# JTAG_Connector.net
KiCad netlist of a schematic drawn in Altium Designer
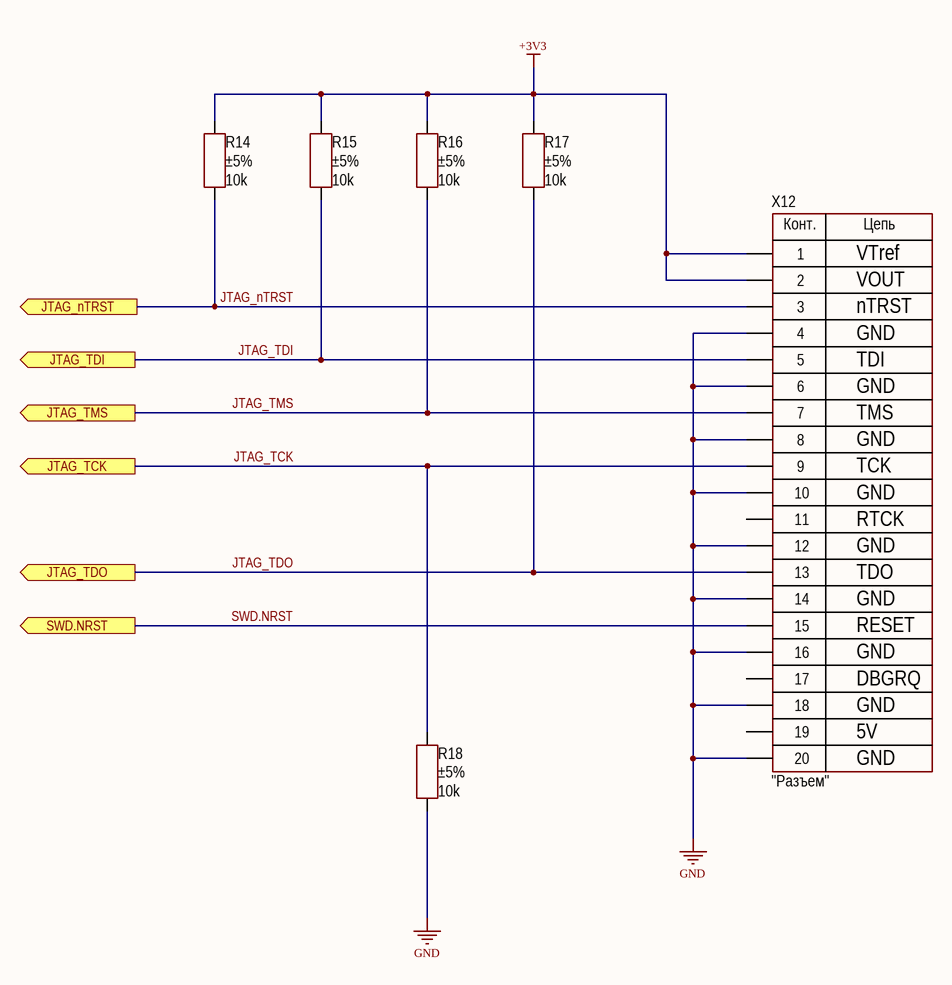
[diagram p0: JTAG_Connector.SchDoc]

(export (version "E")
  (design (tool "Eeschema 10.0.6"))
  (components
    (comp (ref "R14")
      (value "10k")
      (footprint "standard-case:RES: 1206")
      (fields
        (field (name "MANUFACTURER") "Yageo")
        (field (name "PARTNUMBER") "RC1206JR-07100RL")
        (field (name "VALUEMANUFACTURERPARTNUMBER") "Resistor film, 10k, ±5%, 1206, 0.25W, -55...+125°C")
        (field (name "TOLERANCE") "±5%")
      )
      (libsource (lib "resistor") (part "Resistor_1206"))
    )
    (comp (ref "R15")
      (value "10k")
      (footprint "standard-case:RES: 1206")
      (fields
        (field (name "MANUFACTURER") "Yageo")
        (field (name "PARTNUMBER") "RC1206JR-07100RL")
        (field (name "VALUEMANUFACTURERPARTNUMBER") "Resistor film, 10k, ±5%, 1206, 0.25W, -55...+125°C")
        (field (name "TOLERANCE") "±5%")
      )
      (libsource (lib "resistor") (part "Resistor_1206"))
    )
    (comp (ref "R16")
      (value "10k")
      (footprint "standard-case:RES: 1206")
      (fields
        (field (name "MANUFACTURER") "Yageo")
        (field (name "PARTNUMBER") "RC1206JR-07100RL")
        (field (name "VALUEMANUFACTURERPARTNUMBER") "Resistor film, 10k, ±5%, 1206, 0.25W, -55...+125°C")
        (field (name "TOLERANCE") "±5%")
      )
      (libsource (lib "resistor") (part "Resistor_1206"))
    )
    (comp (ref "R17")
      (value "10k")
      (footprint "standard-case:RES: 1206")
      (fields
        (field (name "MANUFACTURER") "Yageo")
        (field (name "PARTNUMBER") "RC1206JR-07100RL")
        (field (name "VALUEMANUFACTURERPARTNUMBER") "Resistor film, 10k, ±5%, 1206, 0.25W, -55...+125°C")
        (field (name "TOLERANCE") "±5%")
      )
      (libsource (lib "resistor") (part "Resistor_1206"))
    )
    (comp (ref "R18")
      (value "10k")
      (footprint "standard-case:RES: 1206")
      (fields
        (field (name "MANUFACTURER") "Yageo")
        (field (name "PARTNUMBER") "RC1206JR-07100RL")
        (field (name "VALUEMANUFACTURERPARTNUMBER") "Resistor film, 10k, ±5%, 1206, 0.25W, -55...+125°C")
        (field (name "TOLERANCE") "±5%")
      )
      (libsource (lib "resistor") (part "Resistor_1206"))
    )
    (comp (ref "X12")
      (value "~")
      (footprint "custom-case:CON: IDC-20MS")
      (fields
        (field (name "MANUFACTURER") "Connfly")
        (field (name "VALUEMANUFACTURERPARTNUMBER") "Connector, 20pin, 2.54mm, 250VAC, 3A")
        (field (name "PARTNUMBER") "IDC-20")
        (field (name "COMMENTTEXT") "\"Разъем\"")
      )
      (libsource (lib "connector") (part "IDC-20"))
    )
  )
  (nets
    (net (code "1") (name "+3V3") (class "Default")
      (node (ref "R14") (pin "2") (pinfunction "2_2") (pintype "passive"))
      (node (ref "R15") (pin "2") (pinfunction "2_2") (pintype "passive"))
      (node (ref "R16") (pin "2") (pinfunction "2_2") (pintype "passive"))
      (node (ref "R17") (pin "2") (pinfunction "2_2") (pintype "passive"))
      (node (ref "X12") (pin "1") (pinfunction "1_1") (pintype "passive"))
      (node (ref "X12") (pin "2") (pinfunction "2_2") (pintype "passive"))
    )
    (net (code "2") (name "/JTAG_TCK") (class "Default")
      (node (ref "R18") (pin "2") (pinfunction "2_2") (pintype "passive"))
      (node (ref "X12") (pin "9") (pinfunction "9_9") (pintype "passive"))
    )
    (net (code "3") (name "/JTAG_TDI") (class "Default")
      (node (ref "R15") (pin "1") (pinfunction "1_1") (pintype "passive"))
      (node (ref "X12") (pin "5") (pinfunction "5_5") (pintype "passive"))
    )
    (net (code "4") (name "/JTAG_TDO") (class "Default")
      (node (ref "R17") (pin "1") (pinfunction "1_1") (pintype "passive"))
      (node (ref "X12") (pin "13") (pinfunction "13_13") (pintype "passive"))
    )
    (net (code "5") (name "/JTAG_TMS") (class "Default")
      (node (ref "R16") (pin "1") (pinfunction "1_1") (pintype "passive"))
      (node (ref "X12") (pin "7") (pinfunction "7_7") (pintype "passive"))
    )
    (net (code "6") (name "/JTAG_nTRST") (class "Default")
      (node (ref "R14") (pin "1") (pinfunction "1_1") (pintype "passive"))
      (node (ref "X12") (pin "3") (pinfunction "3_3") (pintype "passive"))
    )
    (net (code "7") (name "/SWD.NRST") (class "Default")
      (node (ref "X12") (pin "15") (pinfunction "15_15") (pintype "passive"))
    )
    (net (code "8") (name "GND") (class "Default")
      (node (ref "R18") (pin "1") (pinfunction "1_1") (pintype "passive"))
      (node (ref "X12") (pin "10") (pinfunction "10_10") (pintype "passive"))
      (node (ref "X12") (pin "12") (pinfunction "12_12") (pintype "passive"))
      (node (ref "X12") (pin "14") (pinfunction "14_14") (pintype "passive"))
      (node (ref "X12") (pin "16") (pinfunction "16_16") (pintype "passive"))
      (node (ref "X12") (pin "18") (pinfunction "18_18") (pintype "passive"))
      (node (ref "X12") (pin "20") (pinfunction "20_20") (pintype "passive"))
      (node (ref "X12") (pin "4") (pinfunction "4_4") (pintype "passive"))
      (node (ref "X12") (pin "6") (pinfunction "6_6") (pintype "passive"))
      (node (ref "X12") (pin "8") (pinfunction "8_8") (pintype "passive"))
    )
    (net (code "9") (name "unconnected-(X12-Pad11)") (class "Default")
      (node (ref "X12") (pin "11") (pinfunction "11_11") (pintype "passive"))
    )
    (net (code "10") (name "unconnected-(X12-Pad17)") (class "Default")
      (node (ref "X12") (pin "17") (pinfunction "17_17") (pintype "passive"))
    )
    (net (code "11") (name "unconnected-(X12-Pad19)") (class "Default")
      (node (ref "X12") (pin "19") (pinfunction "19_19") (pintype "passive"))
    )
  )
)
